# ledbrick.net
KiCad netlist of a schematic drawn in Altium Designer
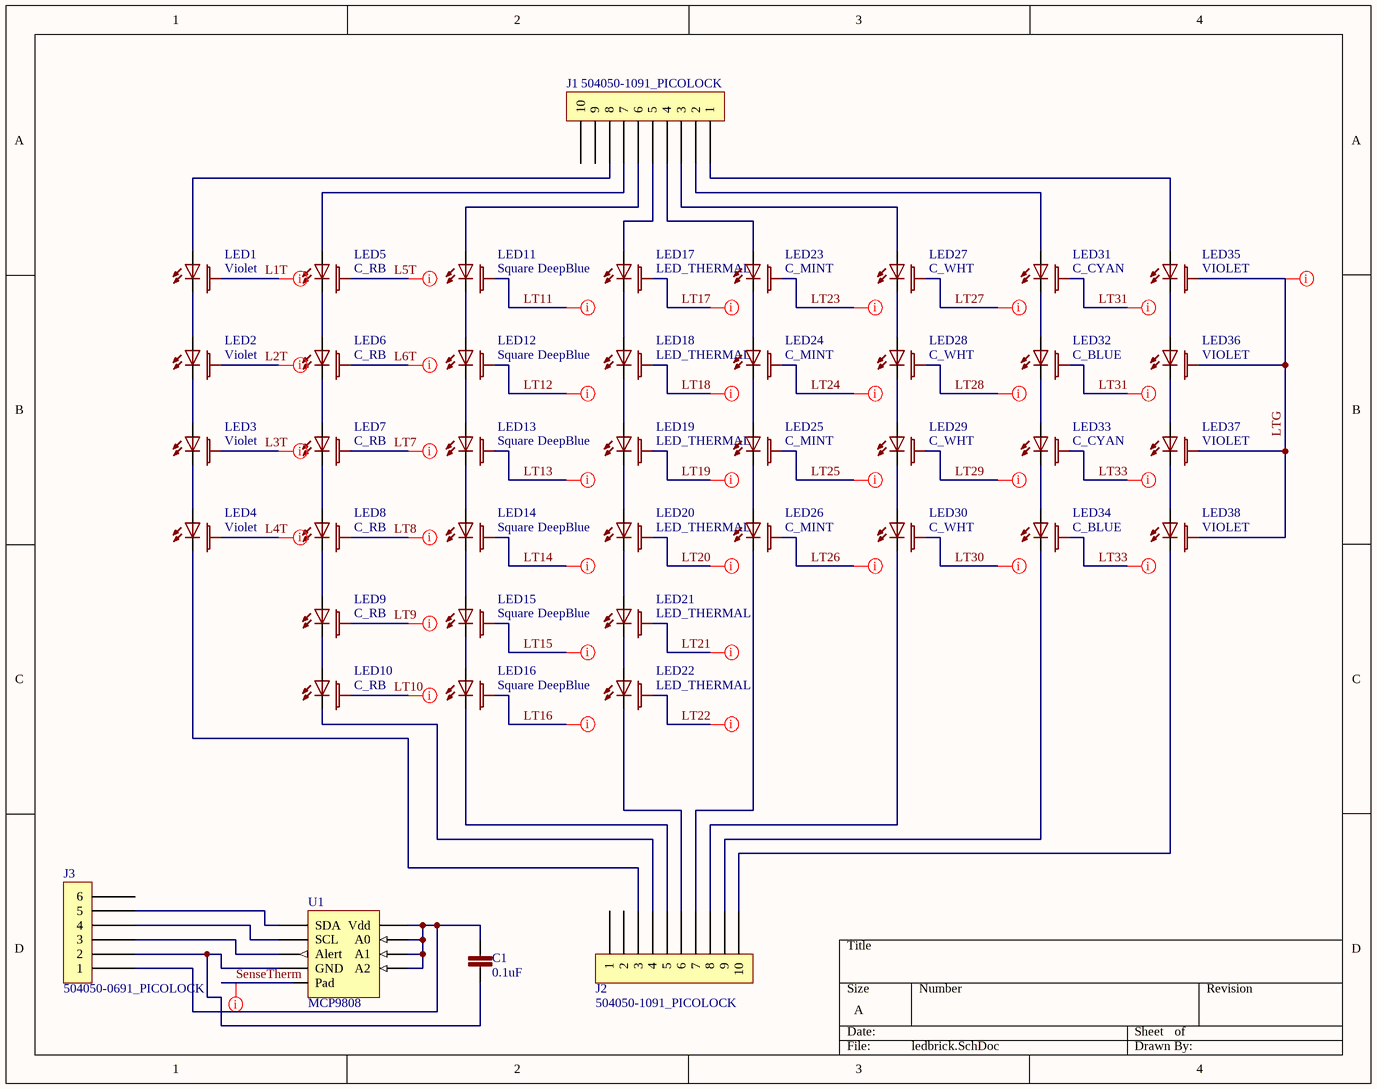
[diagram p0: ledbrick.SchDoc]

(export (version "E")
  (design (tool "Eeschema 10.0.6"))
  (components
    (comp (ref "C1") (value "0.1uF") (footprint "C0603") (libsource (lib "rcl") (part "C-EU")))
    (comp (ref "J1")
      (value "504050-1091_PICOLOCK")
      (footprint "504050-1091_PICOLOCK")
      (libsource (lib "connectors") (part "504050-1091_PICOLOCK"))
    )
    (comp (ref "J2")
      (value "504050-1091_PICOLOCK")
      (footprint "504050-1091_PICOLOCK")
      (libsource (lib "") (part "504050-1091_PICOLOCK_1"))
    )
    (comp (ref "J3")
      (value "504050-0691_PICOLOCK")
      (footprint "504050-0691_PICOLOCK")
      (libsource (lib "connectors") (part "504050-0691_PICOLOCK"))
    )
    (comp (ref "LED1")
      (value "Violet")
      (footprint "SEMILED_3535")
      (libsource (lib "led") (part "LED_THERMAL"))
    )
    (comp (ref "LED2")
      (value "Violet")
      (footprint "SEMILED_3535")
      (libsource (lib "led") (part "LED_THERMAL"))
    )
    (comp (ref "LED3")
      (value "Violet")
      (footprint "SEMILED_3535")
      (libsource (lib "led") (part "LED_THERMAL"))
    )
    (comp (ref "LED4")
      (value "Violet")
      (footprint "SEMILED_3535")
      (libsource (lib "led") (part "LED_THERMAL"))
    )
    (comp (ref "LED5") (value "C_RB") (footprint "LUXEON_C") (libsource (lib "led") (part "LED_THERMAL")))
    (comp (ref "LED6") (value "C_RB") (footprint "LUXEON_C") (libsource (lib "led") (part "LED_THERMAL")))
    (comp (ref "LED7") (value "C_RB") (footprint "LUXEON_C") (libsource (lib "led") (part "LED_THERMAL")))
    (comp (ref "LED8") (value "C_RB") (footprint "LUXEON_C") (libsource (lib "led") (part "LED_THERMAL")))
    (comp (ref "LED9") (value "C_RB") (footprint "LUXEON_C") (libsource (lib "led") (part "LED_THERMAL")))
    (comp (ref "LED10") (value "C_RB") (footprint "LUXEON_C") (libsource (lib "led") (part "LED_THERMAL")))
    (comp (ref "LED11")
      (value "Square DeepBlue")
      (footprint "OSRAM_OSLON_SQUARE")
      (libsource (lib "general") (part "LED_THERMAL"))
    )
    (comp (ref "LED12")
      (value "Square DeepBlue")
      (footprint "OSRAM_OSLON_SQUARE")
      (libsource (lib "general") (part "LED_THERMAL"))
    )
    (comp (ref "LED13")
      (value "Square DeepBlue")
      (footprint "OSRAM_OSLON_SQUARE")
      (libsource (lib "general") (part "LED_THERMAL"))
    )
    (comp (ref "LED14")
      (value "Square DeepBlue")
      (footprint "OSRAM_OSLON_SQUARE")
      (libsource (lib "general") (part "LED_THERMAL"))
    )
    (comp (ref "LED15")
      (value "Square DeepBlue")
      (footprint "OSRAM_OSLON_SQUARE")
      (libsource (lib "general") (part "LED_THERMAL"))
    )
    (comp (ref "LED16")
      (value "Square DeepBlue")
      (footprint "OSRAM_OSLON_SQUARE")
      (libsource (lib "general") (part "LED_THERMAL"))
    )
    (comp (ref "LED17")
      (value "LED_THERMAL")
      (footprint "LUXEON_C")
      (libsource (lib "led") (part "LED_THERMAL"))
    )
    (comp (ref "LED18")
      (value "LED_THERMAL")
      (footprint "LUXEON_C")
      (libsource (lib "led") (part "LED_THERMAL"))
    )
    (comp (ref "LED19")
      (value "LED_THERMAL")
      (footprint "LUXEON_C")
      (libsource (lib "led") (part "LED_THERMAL"))
    )
    (comp (ref "LED20")
      (value "LED_THERMAL")
      (footprint "LUXEON_C")
      (libsource (lib "led") (part "LED_THERMAL"))
    )
    (comp (ref "LED21")
      (value "LED_THERMAL")
      (footprint "LUXEON_C")
      (libsource (lib "led") (part "LED_THERMAL"))
    )
    (comp (ref "LED22")
      (value "LED_THERMAL")
      (footprint "LUXEON_C")
      (libsource (lib "led") (part "LED_THERMAL"))
    )
    (comp (ref "LED23") (value "C_MINT") (footprint "LUXEON_C") (libsource (lib "led") (part "LED_THERMAL")))
    (comp (ref "LED24") (value "C_MINT") (footprint "LUXEON_C") (libsource (lib "led") (part "LED_THERMAL")))
    (comp (ref "LED25") (value "C_MINT") (footprint "LUXEON_C") (libsource (lib "led") (part "LED_THERMAL")))
    (comp (ref "LED26") (value "C_MINT") (footprint "LUXEON_C") (libsource (lib "led") (part "LED_THERMAL")))
    (comp (ref "LED27") (value "C_WHT") (footprint "LUXEON_C") (libsource (lib "led") (part "LED_THERMAL")))
    (comp (ref "LED28") (value "C_WHT") (footprint "LUXEON_C") (libsource (lib "led") (part "LED_THERMAL")))
    (comp (ref "LED29") (value "C_WHT") (footprint "LUXEON_C") (libsource (lib "led") (part "LED_THERMAL")))
    (comp (ref "LED30") (value "C_WHT") (footprint "LUXEON_C") (libsource (lib "led") (part "LED_THERMAL")))
    (comp (ref "LED31") (value "C_CYAN") (footprint "LUXEON_C") (libsource (lib "led") (part "LED_THERMAL")))
    (comp (ref "LED32") (value "C_BLUE") (footprint "LUXEON_C") (libsource (lib "led") (part "LED_THERMAL")))
    (comp (ref "LED33") (value "C_CYAN") (footprint "LUXEON_C") (libsource (lib "led") (part "LED_THERMAL")))
    (comp (ref "LED34") (value "C_BLUE") (footprint "LUXEON_C") (libsource (lib "led") (part "LED_THERMAL")))
    (comp (ref "LED35")
      (value "VIOLET")
      (footprint "SEMILED_3535")
      (libsource (lib "led") (part "LED_THERMAL"))
    )
    (comp (ref "LED36")
      (value "VIOLET")
      (footprint "SEMILED_3535")
      (libsource (lib "led") (part "LED_THERMAL"))
    )
    (comp (ref "LED37")
      (value "VIOLET")
      (footprint "SEMILED_3535")
      (libsource (lib "led") (part "LED_THERMAL"))
    )
    (comp (ref "LED38")
      (value "VIOLET")
      (footprint "SEMILED_3535")
      (libsource (lib "led") (part "LED_THERMAL"))
    )
    (comp (ref "U1") (value "MCP9808") (footprint "DFN8") (libsource (lib "general") (part "MCP9808")))
  )
  (nets
    (net (code "1") (name "/L1T") (class "Default")
      (node (ref "LED1") (pin "PAD") (pinfunction "PAD_PAD") (pintype "passive"))
    )
    (net (code "2") (name "/L2T") (class "Default")
      (node (ref "LED2") (pin "PAD") (pinfunction "PAD_PAD") (pintype "passive"))
    )
    (net (code "3") (name "/L3T") (class "Default")
      (node (ref "LED3") (pin "PAD") (pinfunction "PAD_PAD") (pintype "passive"))
    )
    (net (code "4") (name "/L4T") (class "Default")
      (node (ref "LED4") (pin "PAD") (pinfunction "PAD_PAD") (pintype "passive"))
    )
    (net (code "5") (name "/L5T") (class "Default")
      (node (ref "LED5") (pin "PAD") (pinfunction "PAD_PAD") (pintype "passive"))
    )
    (net (code "6") (name "/L6T") (class "Default")
      (node (ref "LED6") (pin "PAD") (pinfunction "PAD_PAD") (pintype "passive"))
    )
    (net (code "7") (name "/LT7") (class "Default")
      (node (ref "LED7") (pin "PAD") (pinfunction "PAD_PAD") (pintype "passive"))
    )
    (net (code "8") (name "/LT8") (class "Default")
      (node (ref "LED8") (pin "PAD") (pinfunction "PAD_PAD") (pintype "passive"))
    )
    (net (code "9") (name "/LT9") (class "Default")
      (node (ref "LED9") (pin "PAD") (pinfunction "PAD_PAD") (pintype "passive"))
    )
    (net (code "10") (name "/LT10") (class "Default")
      (node (ref "LED10") (pin "PAD") (pinfunction "PAD_PAD") (pintype "passive"))
    )
    (net (code "11") (name "/LT11") (class "Default")
      (node (ref "LED11") (pin "PAD") (pinfunction "PAD_PAD") (pintype "passive"))
    )
    (net (code "12") (name "/LT12") (class "Default")
      (node (ref "LED12") (pin "PAD") (pinfunction "PAD_PAD") (pintype "passive"))
    )
    (net (code "13") (name "/LT13") (class "Default")
      (node (ref "LED13") (pin "PAD") (pinfunction "PAD_PAD") (pintype "passive"))
    )
    (net (code "14") (name "/LT14") (class "Default")
      (node (ref "LED14") (pin "PAD") (pinfunction "PAD_PAD") (pintype "passive"))
    )
    (net (code "15") (name "/LT15") (class "Default")
      (node (ref "LED15") (pin "PAD") (pinfunction "PAD_PAD") (pintype "passive"))
    )
    (net (code "16") (name "/LT16") (class "Default")
      (node (ref "LED16") (pin "PAD") (pinfunction "PAD_PAD") (pintype "passive"))
    )
    (net (code "17") (name "/LT17") (class "Default")
      (node (ref "LED17") (pin "PAD") (pinfunction "PAD_PAD") (pintype "passive"))
    )
    (net (code "18") (name "/LT18") (class "Default")
      (node (ref "LED18") (pin "PAD") (pinfunction "PAD_PAD") (pintype "passive"))
    )
    (net (code "19") (name "/LT19") (class "Default")
      (node (ref "LED19") (pin "PAD") (pinfunction "PAD_PAD") (pintype "passive"))
    )
    (net (code "20") (name "/LT20") (class "Default")
      (node (ref "LED20") (pin "PAD") (pinfunction "PAD_PAD") (pintype "passive"))
    )
    (net (code "21") (name "/LT21") (class "Default")
      (node (ref "LED21") (pin "PAD") (pinfunction "PAD_PAD") (pintype "passive"))
    )
    (net (code "22") (name "/LT22") (class "Default")
      (node (ref "LED22") (pin "PAD") (pinfunction "PAD_PAD") (pintype "passive"))
    )
    (net (code "23") (name "/LT23") (class "Default")
      (node (ref "LED23") (pin "PAD") (pinfunction "PAD_PAD") (pintype "passive"))
    )
    (net (code "24") (name "/LT24") (class "Default")
      (node (ref "LED24") (pin "PAD") (pinfunction "PAD_PAD") (pintype "passive"))
    )
    (net (code "25") (name "/LT25") (class "Default")
      (node (ref "LED25") (pin "PAD") (pinfunction "PAD_PAD") (pintype "passive"))
    )
    (net (code "26") (name "/LT26") (class "Default")
      (node (ref "LED26") (pin "PAD") (pinfunction "PAD_PAD") (pintype "passive"))
    )
    (net (code "27") (name "/LT27") (class "Default")
      (node (ref "LED27") (pin "PAD") (pinfunction "PAD_PAD") (pintype "passive"))
    )
    (net (code "28") (name "/LT28") (class "Default")
      (node (ref "LED28") (pin "PAD") (pinfunction "PAD_PAD") (pintype "passive"))
    )
    (net (code "29") (name "/LT29") (class "Default")
      (node (ref "LED29") (pin "PAD") (pinfunction "PAD_PAD") (pintype "passive"))
    )
    (net (code "30") (name "/LT30") (class "Default")
      (node (ref "LED30") (pin "PAD") (pinfunction "PAD_PAD") (pintype "passive"))
    )
    (net (code "31") (name "/LT31") (class "Default")
      (node (ref "LED31") (pin "PAD") (pinfunction "PAD_PAD") (pintype "passive"))
      (node (ref "LED32") (pin "PAD") (pinfunction "PAD_PAD") (pintype "passive"))
    )
    (net (code "32") (name "/LT33") (class "Default")
      (node (ref "LED33") (pin "PAD") (pinfunction "PAD_PAD") (pintype "passive"))
      (node (ref "LED34") (pin "PAD") (pinfunction "PAD_PAD") (pintype "passive"))
    )
    (net (code "33") (name "/LTG") (class "Default")
      (node (ref "LED35") (pin "PAD") (pinfunction "PAD_PAD") (pintype "passive"))
      (node (ref "LED36") (pin "PAD") (pinfunction "PAD_PAD") (pintype "passive"))
      (node (ref "LED37") (pin "PAD") (pinfunction "PAD_PAD") (pintype "passive"))
      (node (ref "LED38") (pin "PAD") (pinfunction "PAD_PAD") (pintype "passive"))
    )
    (net (code "34") (name "/SenseTherm") (class "Default")
      (node (ref "U1") (pin "PAD") (pinfunction "Pad_PAD") (pintype "power_in"))
    )
    (net (code "35") (name "Net-(J1-Pad1)") (class "Default")
      (node (ref "J1") (pin "1") (pinfunction "1_1") (pintype "passive"))
      (node (ref "LED35") (pin "A") (pinfunction "A_A") (pintype "passive"))
    )
    (net (code "36") (name "Net-(J1-Pad2)") (class "Default")
      (node (ref "J1") (pin "2") (pinfunction "2_2") (pintype "passive"))
      (node (ref "LED31") (pin "A") (pinfunction "A_A") (pintype "passive"))
    )
    (net (code "37") (name "Net-(J1-Pad3)") (class "Default")
      (node (ref "J1") (pin "3") (pinfunction "3_3") (pintype "passive"))
      (node (ref "LED27") (pin "A") (pinfunction "A_A") (pintype "passive"))
    )
    (net (code "38") (name "Net-(J1-Pad4)") (class "Default")
      (node (ref "J1") (pin "4") (pinfunction "4_4") (pintype "passive"))
      (node (ref "LED23") (pin "A") (pinfunction "A_A") (pintype "passive"))
    )
    (net (code "39") (name "Net-(J1-Pad5)") (class "Default")
      (node (ref "J1") (pin "5") (pinfunction "5_5") (pintype "passive"))
      (node (ref "LED17") (pin "A") (pinfunction "A_A") (pintype "passive"))
    )
    (net (code "40") (name "Net-(J1-Pad6)") (class "Default")
      (node (ref "J1") (pin "6") (pinfunction "6_6") (pintype "passive"))
      (node (ref "LED11") (pin "A") (pinfunction "A_A") (pintype "passive"))
    )
    (net (code "41") (name "Net-(J1-Pad7)") (class "Default")
      (node (ref "J1") (pin "7") (pinfunction "7_7") (pintype "passive"))
      (node (ref "LED5") (pin "A") (pinfunction "A_A") (pintype "passive"))
    )
    (net (code "42") (name "Net-(J1-Pad8)") (class "Default")
      (node (ref "J1") (pin "8") (pinfunction "8_8") (pintype "passive"))
      (node (ref "LED1") (pin "A") (pinfunction "A_A") (pintype "passive"))
    )
    (net (code "43") (name "Net-(J2-Pad3)") (class "Default")
      (node (ref "J2") (pin "3") (pinfunction "3_3") (pintype "passive"))
      (node (ref "LED4") (pin "C") (pinfunction "C_C") (pintype "passive"))
    )
    (net (code "44") (name "Net-(J2-Pad4)") (class "Default")
      (node (ref "J2") (pin "4") (pinfunction "4_4") (pintype "passive"))
      (node (ref "LED10") (pin "C") (pinfunction "C_C") (pintype "passive"))
    )
    (net (code "45") (name "Net-(J2-Pad5)") (class "Default")
      (node (ref "J2") (pin "5") (pinfunction "5_5") (pintype "passive"))
      (node (ref "LED16") (pin "C") (pinfunction "C_C") (pintype "passive"))
    )
    (net (code "46") (name "Net-(J2-Pad6)") (class "Default")
      (node (ref "J2") (pin "6") (pinfunction "6_6") (pintype "passive"))
      (node (ref "LED22") (pin "C") (pinfunction "C_C") (pintype "passive"))
    )
    (net (code "47") (name "Net-(J2-Pad7)") (class "Default")
      (node (ref "J2") (pin "7") (pinfunction "7_7") (pintype "passive"))
      (node (ref "LED26") (pin "C") (pinfunction "C_C") (pintype "passive"))
    )
    (net (code "48") (name "Net-(J2-Pad8)") (class "Default")
      (node (ref "J2") (pin "8") (pinfunction "8_8") (pintype "passive"))
      (node (ref "LED30") (pin "C") (pinfunction "C_C") (pintype "passive"))
    )
    (net (code "49") (name "Net-(J2-Pad9)") (class "Default")
      (node (ref "J2") (pin "9") (pinfunction "9_9") (pintype "passive"))
      (node (ref "LED34") (pin "C") (pinfunction "C_C") (pintype "passive"))
    )
    (net (code "50") (name "Net-(J2-Pad10)") (class "Default")
      (node (ref "J2") (pin "10") (pinfunction "10_10") (pintype "passive"))
      (node (ref "LED38") (pin "C") (pinfunction "C_C") (pintype "passive"))
    )
    (net (code "51") (name "Net-(LED1-PadC)") (class "Default")
      (node (ref "LED1") (pin "C") (pinfunction "C_C") (pintype "passive"))
      (node (ref "LED2") (pin "A") (pinfunction "A_A") (pintype "passive"))
    )
    (net (code "52") (name "Net-(LED2-PadC)") (class "Default")
      (node (ref "LED2") (pin "C") (pinfunction "C_C") (pintype "passive"))
      (node (ref "LED3") (pin "A") (pinfunction "A_A") (pintype "passive"))
    )
    (net (code "53") (name "Net-(LED3-PadC)") (class "Default")
      (node (ref "LED3") (pin "C") (pinfunction "C_C") (pintype "passive"))
      (node (ref "LED4") (pin "A") (pinfunction "A_A") (pintype "passive"))
    )
    (net (code "54") (name "Net-(LED5-PadC)") (class "Default")
      (node (ref "LED5") (pin "C") (pinfunction "C_C") (pintype "passive"))
      (node (ref "LED6") (pin "A") (pinfunction "A_A") (pintype "passive"))
    )
    (net (code "55") (name "Net-(LED6-PadC)") (class "Default")
      (node (ref "LED6") (pin "C") (pinfunction "C_C") (pintype "passive"))
      (node (ref "LED7") (pin "A") (pinfunction "A_A") (pintype "passive"))
    )
    (net (code "56") (name "Net-(LED7-PadC)") (class "Default")
      (node (ref "LED7") (pin "C") (pinfunction "C_C") (pintype "passive"))
      (node (ref "LED8") (pin "A") (pinfunction "A_A") (pintype "passive"))
    )
    (net (code "57") (name "Net-(LED8-PadC)") (class "Default")
      (node (ref "LED8") (pin "C") (pinfunction "C_C") (pintype "passive"))
      (node (ref "LED9") (pin "A") (pinfunction "A_A") (pintype "passive"))
    )
    (net (code "58") (name "Net-(LED10-PadA)") (class "Default")
      (node (ref "LED10") (pin "A") (pinfunction "A_A") (pintype "passive"))
      (node (ref "LED9") (pin "C") (pinfunction "C_C") (pintype "passive"))
    )
    (net (code "59") (name "Net-(LED11-PadC)") (class "Default")
      (node (ref "LED11") (pin "C") (pinfunction "C_C") (pintype "passive"))
      (node (ref "LED12") (pin "A") (pinfunction "A_A") (pintype "passive"))
    )
    (net (code "60") (name "Net-(LED12-PadC)") (class "Default")
      (node (ref "LED12") (pin "C") (pinfunction "C_C") (pintype "passive"))
      (node (ref "LED13") (pin "A") (pinfunction "A_A") (pintype "passive"))
    )
    (net (code "61") (name "Net-(LED13-PadC)") (class "Default")
      (node (ref "LED13") (pin "C") (pinfunction "C_C") (pintype "passive"))
      (node (ref "LED14") (pin "A") (pinfunction "A_A") (pintype "passive"))
    )
    (net (code "62") (name "Net-(LED14-PadC)") (class "Default")
      (node (ref "LED14") (pin "C") (pinfunction "C_C") (pintype "passive"))
      (node (ref "LED15") (pin "A") (pinfunction "A_A") (pintype "passive"))
    )
    (net (code "63") (name "Net-(LED15-PadC)") (class "Default")
      (node (ref "LED15") (pin "C") (pinfunction "C_C") (pintype "passive"))
      (node (ref "LED16") (pin "A") (pinfunction "A_A") (pintype "passive"))
    )
    (net (code "64") (name "Net-(LED17-PadC)") (class "Default")
      (node (ref "LED17") (pin "C") (pinfunction "C_C") (pintype "passive"))
      (node (ref "LED18") (pin "A") (pinfunction "A_A") (pintype "passive"))
    )
    (net (code "65") (name "Net-(LED18-PadC)") (class "Default")
      (node (ref "LED18") (pin "C") (pinfunction "C_C") (pintype "passive"))
      (node (ref "LED19") (pin "A") (pinfunction "A_A") (pintype "passive"))
    )
    (net (code "66") (name "Net-(LED19-PadC)") (class "Default")
      (node (ref "LED19") (pin "C") (pinfunction "C_C") (pintype "passive"))
      (node (ref "LED20") (pin "A") (pinfunction "A_A") (pintype "passive"))
    )
    (net (code "67") (name "Net-(LED20-PadC)") (class "Default")
      (node (ref "LED20") (pin "C") (pinfunction "C_C") (pintype "passive"))
      (node (ref "LED21") (pin "A") (pinfunction "A_A") (pintype "passive"))
    )
    (net (code "68") (name "Net-(LED21-PadC)") (class "Default")
      (node (ref "LED21") (pin "C") (pinfunction "C_C") (pintype "passive"))
      (node (ref "LED22") (pin "A") (pinfunction "A_A") (pintype "passive"))
    )
    (net (code "69") (name "Net-(LED23-PadC)") (class "Default")
      (node (ref "LED23") (pin "C") (pinfunction "C_C") (pintype "passive"))
      (node (ref "LED24") (pin "A") (pinfunction "A_A") (pintype "passive"))
    )
    (net (code "70") (name "Net-(LED24-PadC)") (class "Default")
      (node (ref "LED24") (pin "C") (pinfunction "C_C") (pintype "passive"))
      (node (ref "LED25") (pin "A") (pinfunction "A_A") (pintype "passive"))
    )
    (net (code "71") (name "Net-(LED25-PadC)") (class "Default")
      (node (ref "LED25") (pin "C") (pinfunction "C_C") (pintype "passive"))
      (node (ref "LED26") (pin "A") (pinfunction "A_A") (pintype "passive"))
    )
    (net (code "72") (name "Net-(LED27-PadC)") (class "Default")
      (node (ref "LED27") (pin "C") (pinfunction "C_C") (pintype "passive"))
      (node (ref "LED28") (pin "A") (pinfunction "A_A") (pintype "passive"))
    )
    (net (code "73") (name "Net-(LED28-PadC)") (class "Default")
      (node (ref "LED28") (pin "C") (pinfunction "C_C") (pintype "passive"))
      (node (ref "LED29") (pin "A") (pinfunction "A_A") (pintype "passive"))
    )
    (net (code "74") (name "Net-(LED29-PadC)") (class "Default")
      (node (ref "LED29") (pin "C") (pinfunction "C_C") (pintype "passive"))
      (node (ref "LED30") (pin "A") (pinfunction "A_A") (pintype "passive"))
    )
    (net (code "75") (name "Net-(LED31-PadC)") (class "Default")
      (node (ref "LED31") (pin "C") (pinfunction "C_C") (pintype "passive"))
      (node (ref "LED32") (pin "A") (pinfunction "A_A") (pintype "passive"))
    )
    (net (code "76") (name "Net-(LED32-PadC)") (class "Default")
      (node (ref "LED32") (pin "C") (pinfunction "C_C") (pintype "passive"))
      (node (ref "LED33") (pin "A") (pinfunction "A_A") (pintype "passive"))
    )
    (net (code "77") (name "Net-(LED33-PadC)") (class "Default")
      (node (ref "LED33") (pin "C") (pinfunction "C_C") (pintype "passive"))
      (node (ref "LED34") (pin "A") (pinfunction "A_A") (pintype "passive"))
    )
    (net (code "78") (name "Net-(LED35-PadC)") (class "Default")
      (node (ref "LED35") (pin "C") (pinfunction "C_C") (pintype "passive"))
      (node (ref "LED36") (pin "A") (pinfunction "A_A") (pintype "passive"))
    )
    (net (code "79") (name "Net-(LED36-PadC)") (class "Default")
      (node (ref "LED36") (pin "C") (pinfunction "C_C") (pintype "passive"))
      (node (ref "LED37") (pin "A") (pinfunction "A_A") (pintype "passive"))
    )
    (net (code "80") (name "Net-(LED37-PadC)") (class "Default")
      (node (ref "LED37") (pin "C") (pinfunction "C_C") (pintype "passive"))
      (node (ref "LED38") (pin "A") (pinfunction "A_A") (pintype "passive"))
    )
    (net (code "81") (name "Net-(U1-A0)") (class "Default")
      (node (ref "C1") (pin "1") (pinfunction "1_1") (pintype "passive"))
      (node (ref "J3") (pin "1") (pinfunction "1_1") (pintype "passive"))
      (node (ref "U1") (pin "5") (pinfunction "A2_5") (pintype "input"))
      (node (ref "U1") (pin "6") (pinfunction "A1_6") (pintype "input"))
      (node (ref "U1") (pin "7") (pinfunction "A0_7") (pintype "input"))
      (node (ref "U1") (pin "8") (pinfunction "Vdd_8") (pintype "power_in"))
    )
    (net (code "82") (name "Net-(U1-Alert)") (class "Default")
      (node (ref "J3") (pin "3") (pinfunction "3_3") (pintype "passive"))
      (node (ref "U1") (pin "3") (pinfunction "Alert_3") (pintype "output"))
    )
    (net (code "83") (name "Net-(U1-GND)") (class "Default")
      (node (ref "C1") (pin "2") (pinfunction "2_2") (pintype "passive"))
      (node (ref "J3") (pin "2") (pinfunction "2_2") (pintype "passive"))
      (node (ref "U1") (pin "4") (pinfunction "GND_4") (pintype "power_in"))
    )
    (net (code "84") (name "Net-(U1-SCL)") (class "Default")
      (node (ref "J3") (pin "4") (pinfunction "4_4") (pintype "passive"))
      (node (ref "U1") (pin "2") (pinfunction "SCL_2") (pintype "open_collector"))
    )
    (net (code "85") (name "Net-(U1-SDA)") (class "Default")
      (node (ref "J3") (pin "5") (pinfunction "5_5") (pintype "passive"))
      (node (ref "U1") (pin "1") (pinfunction "SDA_1") (pintype "open_collector"))
    )
    (net (code "86") (name "unconnected-(J1-Pad9)") (class "Default")
      (node (ref "J1") (pin "9") (pinfunction "9_9") (pintype "passive"))
    )
    (net (code "87") (name "unconnected-(J1-Pad10)") (class "Default")
      (node (ref "J1") (pin "10") (pinfunction "10_10") (pintype "passive"))
    )
    (net (code "88") (name "unconnected-(J2-Pad1)") (class "Default")
      (node (ref "J2") (pin "1") (pinfunction "1_1") (pintype "passive"))
    )
    (net (code "89") (name "unconnected-(J2-Pad2)") (class "Default")
      (node (ref "J2") (pin "2") (pinfunction "2_2") (pintype "passive"))
    )
    (net (code "90") (name "unconnected-(J3-Pad6)") (class "Default")
      (node (ref "J3") (pin "6") (pinfunction "6_6") (pintype "passive"))
    )
  )
)
